# Power.net
KiCad netlist of a schematic drawn in Altium Designer
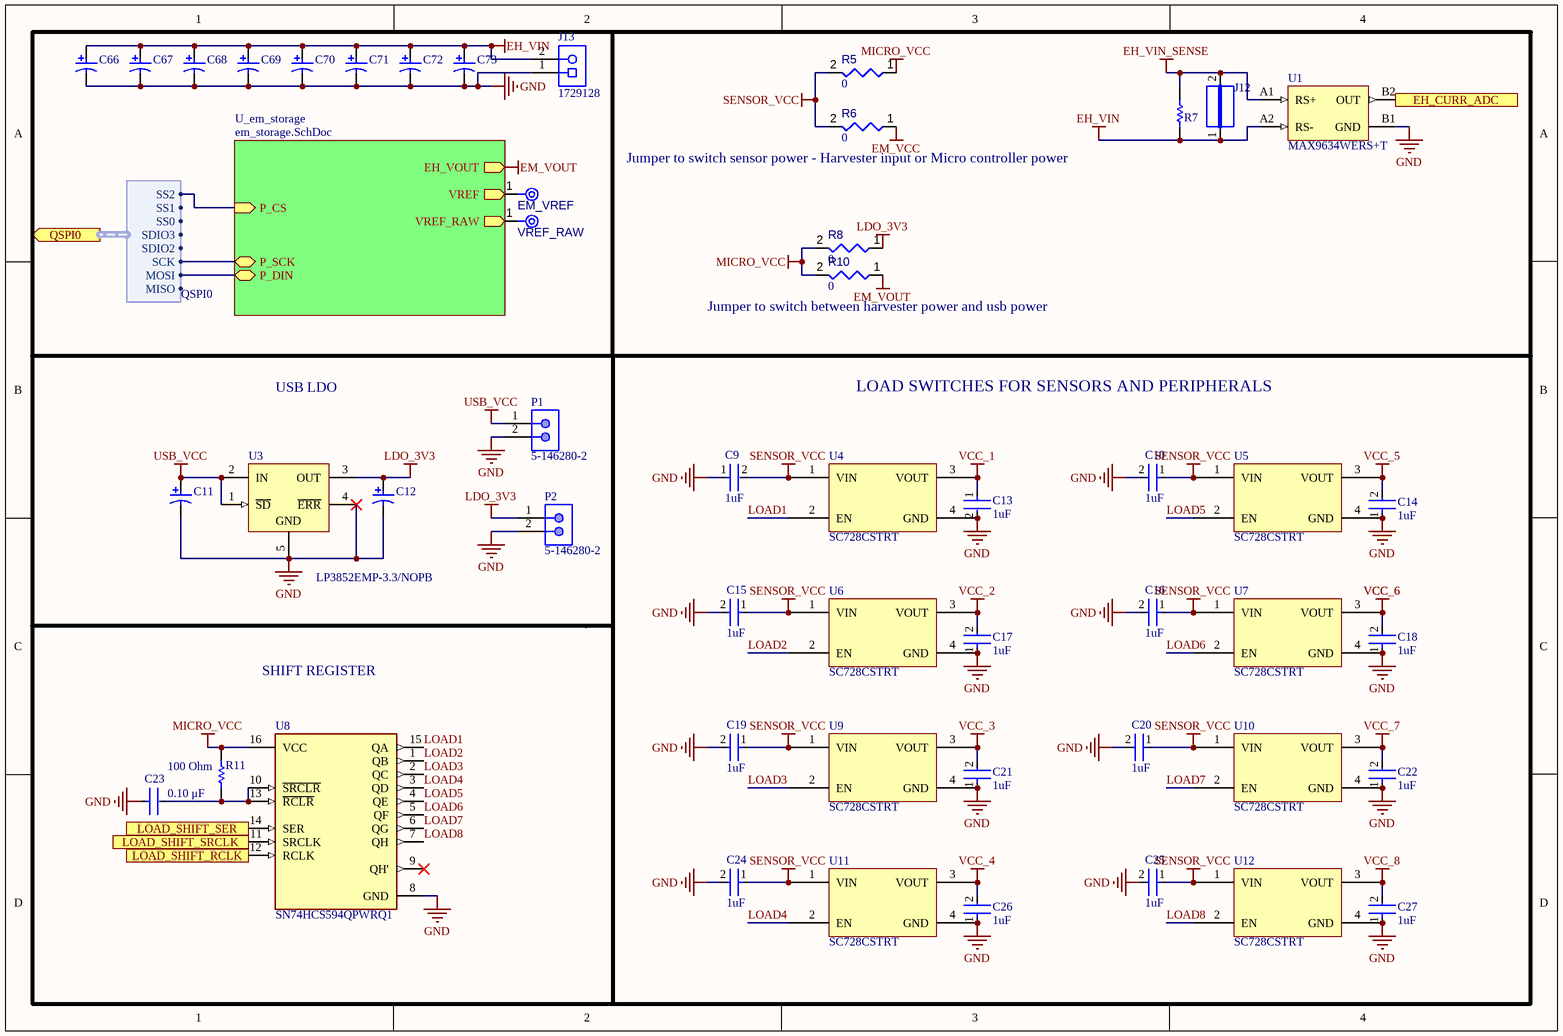
[diagram p0: Power.SchDoc]

(export (version "E")
  (design (tool "Eeschema 10.0.6"))
  (components
    (comp (ref "C9")
      (value "GRT155R61C105KE01J")
      (footprint "FP-GRM15-0_1-MFG")
      (description "CAP CER 1UF 10V X5R 0402")
      (fields
        (field (name "OCTOPART") "https://octopart.com/grm155r61a105ke15d-murata-197442")
        (field (name "MANUFACTURER PART NUMBER") "GRM155R61A105KE15D")
        (field (name "CAPACITANCE") "1uF")
      )
      (libsource (lib "Altium Content Vault") (part "02cd4be3c70576c341d710602a673aa"))
    )
    (comp (ref "C10")
      (value "GRT155R61C105KE01J")
      (footprint "FP-GRM15-0_1-MFG")
      (description "CAP CER 1UF 10V X5R 0402")
      (fields
        (field (name "OCTOPART") "https://octopart.com/grm155r61a105ke15d-murata-197442")
        (field (name "MANUFACTURER PART NUMBER") "GRM155R61A105KE15D")
        (field (name "CAPACITANCE") "1uF")
      )
      (libsource (lib "Altium Content Vault") (part "02cd4be3c70576c341d710602a673aa"))
    )
    (comp (ref "C11")
      (value "T491D106K025AT")
      (footprint "KEMT-T491-D_L")
      (description "Tantalum Capacitor, 10 uF, +/- 10%, 25 V, -55 to 125 degC, 2-Pin SMD, RoHS, Tape and Reel")
      (fields (field (name "MANUFACTURER") "Kemet") (field (name "VOLTAGE") "25VDC"))
      (libsource (lib "Altium Content Vault") (part "CAP-P-2"))
    )
    (comp (ref "C12")
      (value "T491D106K025AT")
      (footprint "KEMT-T491-D_L")
      (description "Tantalum Capacitor, 10 uF, +/- 10%, 25 V, -55 to 125 degC, 2-Pin SMD, RoHS, Tape and Reel")
      (fields (field (name "MANUFACTURER") "Kemet") (field (name "VOLTAGE") "25VDC"))
      (libsource (lib "Altium Content Vault") (part "CAP-P-2"))
    )
    (comp (ref "C13")
      (value "GRT155R61C105KE01J")
      (footprint "FP-GRM15-0_1-MFG")
      (description "CAP CER 1UF 10V X5R 0402")
      (fields
        (field (name "OCTOPART") "https://octopart.com/grm155r61a105ke15d-murata-197442")
        (field (name "MANUFACTURER PART NUMBER") "GRM155R61A105KE15D")
        (field (name "CAPACITANCE") "1uF")
      )
      (libsource (lib "Altium Content Vault") (part "02cd4be3c70576c341d710602a673aa"))
    )
    (comp (ref "C14")
      (value "GRT155R61C105KE01J")
      (footprint "FP-GRM15-0_1-MFG")
      (description "CAP CER 1UF 10V X5R 0402")
      (fields
        (field (name "OCTOPART") "https://octopart.com/grm155r61a105ke15d-murata-197442")
        (field (name "MANUFACTURER PART NUMBER") "GRM155R61A105KE15D")
        (field (name "CAPACITANCE") "1uF")
      )
      (libsource (lib "Altium Content Vault") (part "02cd4be3c70576c341d710602a673aa"))
    )
    (comp (ref "C15")
      (value "GRT155R61C105KE01J")
      (footprint "FP-GRM15-0_1-MFG")
      (description "CAP CER 1UF 10V X5R 0402")
      (fields
        (field (name "OCTOPART") "https://octopart.com/grm155r61a105ke15d-murata-197442")
        (field (name "MANUFACTURER PART NUMBER") "GRM155R61A105KE15D")
        (field (name "CAPACITANCE") "1uF")
      )
      (libsource (lib "Altium Content Vault") (part "02cd4be3c70576c341d710602a673aa"))
    )
    (comp (ref "C16")
      (value "GRT155R61C105KE01J")
      (footprint "FP-GRM15-0_1-MFG")
      (description "CAP CER 1UF 10V X5R 0402")
      (fields
        (field (name "OCTOPART") "https://octopart.com/grm155r61a105ke15d-murata-197442")
        (field (name "MANUFACTURER PART NUMBER") "GRM155R61A105KE15D")
        (field (name "CAPACITANCE") "1uF")
      )
      (libsource (lib "Altium Content Vault") (part "02cd4be3c70576c341d710602a673aa"))
    )
    (comp (ref "C17")
      (value "GRT155R61C105KE01J")
      (footprint "FP-GRM15-0_1-MFG")
      (description "CAP CER 1UF 10V X5R 0402")
      (fields
        (field (name "OCTOPART") "https://octopart.com/grm155r61a105ke15d-murata-197442")
        (field (name "MANUFACTURER PART NUMBER") "GRM155R61A105KE15D")
        (field (name "CAPACITANCE") "1uF")
      )
      (libsource (lib "Altium Content Vault") (part "02cd4be3c70576c341d710602a673aa"))
    )
    (comp (ref "C18")
      (value "GRT155R61C105KE01J")
      (footprint "FP-GRM15-0_1-MFG")
      (description "CAP CER 1UF 10V X5R 0402")
      (fields
        (field (name "OCTOPART") "https://octopart.com/grm155r61a105ke15d-murata-197442")
        (field (name "MANUFACTURER PART NUMBER") "GRM155R61A105KE15D")
        (field (name "CAPACITANCE") "1uF")
      )
      (libsource (lib "Altium Content Vault") (part "02cd4be3c70576c341d710602a673aa"))
    )
    (comp (ref "C19")
      (value "GRT155R61C105KE01J")
      (footprint "FP-GRM15-0_1-MFG")
      (description "CAP CER 1UF 10V X5R 0402")
      (fields
        (field (name "OCTOPART") "https://octopart.com/grm155r61a105ke15d-murata-197442")
        (field (name "MANUFACTURER PART NUMBER") "GRM155R61A105KE15D")
        (field (name "CAPACITANCE") "1uF")
      )
      (libsource (lib "Altium Content Vault") (part "02cd4be3c70576c341d710602a673aa"))
    )
    (comp (ref "C20")
      (value "GRT155R61C105KE01J")
      (footprint "FP-GRM15-0_1-MFG")
      (description "CAP CER 1UF 10V X5R 0402")
      (fields
        (field (name "OCTOPART") "https://octopart.com/grm155r61a105ke15d-murata-197442")
        (field (name "MANUFACTURER PART NUMBER") "GRM155R61A105KE15D")
        (field (name "CAPACITANCE") "1uF")
      )
      (libsource (lib "Altium Content Vault") (part "02cd4be3c70576c341d710602a673aa"))
    )
    (comp (ref "C21")
      (value "GRT155R61C105KE01J")
      (footprint "FP-GRM15-0_1-MFG")
      (description "CAP CER 1UF 10V X5R 0402")
      (fields
        (field (name "OCTOPART") "https://octopart.com/grm155r61a105ke15d-murata-197442")
        (field (name "MANUFACTURER PART NUMBER") "GRM155R61A105KE15D")
        (field (name "CAPACITANCE") "1uF")
      )
      (libsource (lib "Altium Content Vault") (part "02cd4be3c70576c341d710602a673aa"))
    )
    (comp (ref "C22")
      (value "GRT155R61C105KE01J")
      (footprint "FP-GRM15-0_1-MFG")
      (description "CAP CER 1UF 10V X5R 0402")
      (fields
        (field (name "OCTOPART") "https://octopart.com/grm155r61a105ke15d-murata-197442")
        (field (name "MANUFACTURER PART NUMBER") "GRM155R61A105KE15D")
        (field (name "CAPACITANCE") "1uF")
      )
      (libsource (lib "Altium Content Vault") (part "02cd4be3c70576c341d710602a673aa"))
    )
    (comp (ref "C23")
      (value "C0402C104K8PACTU")
      (footprint "FP-C0402-BB-MFG")
      (description "CAP CER 0.1UF 10V X5R 0402")
      (fields
        (field (name "CAPACITANCE") "0.10 μF")
        (field (name "MANUFACTURER") "Kemet")
        (field (name "TOLERANCE") "0.1")
      )
      (libsource (lib "Altium Content Vault") (part "b4654b650e69147ec39a6b967a45e02"))
    )
    (comp (ref "C24")
      (value "GRT155R61C105KE01J")
      (footprint "FP-GRM15-0_1-MFG")
      (description "CAP CER 1UF 10V X5R 0402")
      (fields
        (field (name "OCTOPART") "https://octopart.com/grm155r61a105ke15d-murata-197442")
        (field (name "MANUFACTURER PART NUMBER") "GRM155R61A105KE15D")
        (field (name "CAPACITANCE") "1uF")
      )
      (libsource (lib "Altium Content Vault") (part "02cd4be3c70576c341d710602a673aa"))
    )
    (comp (ref "C25")
      (value "GRT155R61C105KE01J")
      (footprint "FP-GRM15-0_1-MFG")
      (description "CAP CER 1UF 10V X5R 0402")
      (fields
        (field (name "OCTOPART") "https://octopart.com/grm155r61a105ke15d-murata-197442")
        (field (name "MANUFACTURER PART NUMBER") "GRM155R61A105KE15D")
        (field (name "CAPACITANCE") "1uF")
      )
      (libsource (lib "Altium Content Vault") (part "02cd4be3c70576c341d710602a673aa"))
    )
    (comp (ref "C26")
      (value "GRT155R61C105KE01J")
      (footprint "FP-GRM15-0_1-MFG")
      (description "CAP CER 1UF 10V X5R 0402")
      (fields
        (field (name "OCTOPART") "https://octopart.com/grm155r61a105ke15d-murata-197442")
        (field (name "MANUFACTURER PART NUMBER") "GRM155R61A105KE15D")
        (field (name "CAPACITANCE") "1uF")
      )
      (libsource (lib "Altium Content Vault") (part "02cd4be3c70576c341d710602a673aa"))
    )
    (comp (ref "C27")
      (value "GRT155R61C105KE01J")
      (footprint "FP-GRM15-0_1-MFG")
      (description "CAP CER 1UF 10V X5R 0402")
      (fields
        (field (name "OCTOPART") "https://octopart.com/grm155r61a105ke15d-murata-197442")
        (field (name "MANUFACTURER PART NUMBER") "GRM155R61A105KE15D")
        (field (name "CAPACITANCE") "1uF")
      )
      (libsource (lib "Altium Content Vault") (part "02cd4be3c70576c341d710602a673aa"))
    )
    (comp (ref "C66")
      (value "T491D106K025AT")
      (footprint "KEMT-T491-D_L")
      (description "Tantalum Capacitor, 10 uF, +/- 10%, 25 V, -55 to 125 degC, 2-Pin SMD, RoHS, Tape and Reel")
      (fields (field (name "MANUFACTURER") "Kemet") (field (name "VOLTAGE") "25VDC"))
      (libsource (lib "Altium Content Vault") (part "CAP-P-2"))
    )
    (comp (ref "C67")
      (value "T491D106K025AT")
      (footprint "KEMT-T491-D_L")
      (description "Tantalum Capacitor, 10 uF, +/- 10%, 25 V, -55 to 125 degC, 2-Pin SMD, RoHS, Tape and Reel")
      (fields (field (name "MANUFACTURER") "Kemet") (field (name "VOLTAGE") "25VDC"))
      (libsource (lib "Altium Content Vault") (part "CAP-P-2"))
    )
    (comp (ref "C68")
      (value "T491D106K025AT")
      (footprint "KEMT-T491-D_L")
      (description "Tantalum Capacitor, 10 uF, +/- 10%, 25 V, -55 to 125 degC, 2-Pin SMD, RoHS, Tape and Reel")
      (fields (field (name "MANUFACTURER") "Kemet") (field (name "VOLTAGE") "25VDC"))
      (libsource (lib "Altium Content Vault") (part "CAP-P-2"))
    )
    (comp (ref "C69")
      (value "T491D106K025AT")
      (footprint "KEMT-T491-D_L")
      (description "Tantalum Capacitor, 10 uF, +/- 10%, 25 V, -55 to 125 degC, 2-Pin SMD, RoHS, Tape and Reel")
      (fields (field (name "MANUFACTURER") "Kemet") (field (name "VOLTAGE") "25VDC"))
      (libsource (lib "Altium Content Vault") (part "CAP-P-2"))
    )
    (comp (ref "C70")
      (value "T491D106K025AT")
      (footprint "KEMT-T491-D_L")
      (description "Tantalum Capacitor, 10 uF, +/- 10%, 25 V, -55 to 125 degC, 2-Pin SMD, RoHS, Tape and Reel")
      (fields (field (name "MANUFACTURER") "Kemet") (field (name "VOLTAGE") "25VDC"))
      (libsource (lib "Altium Content Vault") (part "CAP-P-2"))
    )
    (comp (ref "C71")
      (value "T491D106K025AT")
      (footprint "KEMT-T491-D_L")
      (description "Tantalum Capacitor, 10 uF, +/- 10%, 25 V, -55 to 125 degC, 2-Pin SMD, RoHS, Tape and Reel")
      (fields (field (name "MANUFACTURER") "Kemet") (field (name "VOLTAGE") "25VDC"))
      (libsource (lib "Altium Content Vault") (part "CAP-P-2"))
    )
    (comp (ref "C72")
      (value "T491D106K025AT")
      (footprint "KEMT-T491-D_L")
      (description "Tantalum Capacitor, 10 uF, +/- 10%, 25 V, -55 to 125 degC, 2-Pin SMD, RoHS, Tape and Reel")
      (fields (field (name "MANUFACTURER") "Kemet") (field (name "VOLTAGE") "25VDC"))
      (libsource (lib "Altium Content Vault") (part "CAP-P-2"))
    )
    (comp (ref "C73")
      (value "T491D106K025AT")
      (footprint "KEMT-T491-D_L")
      (description "Tantalum Capacitor, 10 uF, +/- 10%, 25 V, -55 to 125 degC, 2-Pin SMD, RoHS, Tape and Reel")
      (fields (field (name "MANUFACTURER") "Kemet") (field (name "VOLTAGE") "25VDC"))
      (libsource (lib "Altium Content Vault") (part "CAP-P-2"))
    )
    (comp (ref "EM_VREF")
      (value "TPAD6R")
      (footprint "TP06R")
      (description "0.6mm round")
      (libsource (lib "Supersensor") (part "CMP-001-0001-4"))
    )
    (comp (ref "J12") (value "JUMPER") (footprint "JUMPER") (libsource (lib "Supersensor") (part "JUMPER")))
    (comp (ref "J13")
      (value "1729128")
      (footprint "PHOE-1729128-2_V")
      (description "PCB Terminal Block, 13.5 A, 400 V, 2-Pin THD, RoHS, Bulk")
      (fields (field (name "MANUFACTURER") "Phoenix Contact"))
      (libsource (lib "Altium Content Vault") (part "CN-2P-F-R2"))
    )
    (comp (ref "P1")
      (value "5-146280-2")
      (footprint "TECO-5-146280-2_V")
      (fields (field (name "MANUFACTURER") "TE Connectivity"))
      (libsource (lib "Altium Content Vault") (part "CN-1P-M-R2"))
    )
    (comp (ref "P2")
      (value "5-146280-2")
      (footprint "TECO-5-146280-2_V")
      (fields (field (name "MANUFACTURER") "TE Connectivity"))
      (libsource (lib "Altium Content Vault") (part "CN-1P-M-R2"))
    )
    (comp (ref "R5")
      (value "0")
      (footprint "RESC0402(1005)_L")
      (description "Jumper 0402")
      (libsource (lib "Supersensor") (part "RES-2"))
    )
    (comp (ref "R6")
      (value "0")
      (footprint "RESC0402(1005)_L")
      (description "Jumper 0402")
      (libsource (lib "Supersensor") (part "RES-2"))
    )
    (comp (ref "R7")
      (value "WSL0603R0300FEA18")
      (footprint "RESC1508X46X38ML25T25")
      (fields (field (name "MANUFACTURER") "Vishay Dale"))
      (libsource (lib "Altium Content Vault") (part "RES"))
    )
    (comp (ref "R8")
      (value "0")
      (footprint "RESC0402(1005)_L")
      (description "Jumper 0402")
      (libsource (lib "Supersensor") (part "RES-2"))
    )
    (comp (ref "R10")
      (value "0")
      (footprint "RESC0402(1005)_L")
      (description "Jumper 0402")
      (libsource (lib "Supersensor") (part "RES-2"))
    )
    (comp (ref "R11")
      (value "ERJ-2RKF1000X")
      (footprint "RESC1005X40X25LL05T05")
      (description "Chip Resistor, 100 Ohm, +/- 1%, 100 mW, -55 to 155 degC, 0402 (1005 Metric), RoHS, Tape and Reel")
      (fields
        (field (name "MANUFACTURER") "Basic Passives")
        (field (name "TOLERANCE") "1%")
        (field (name "RESISTANCE") "100 Ohm")
      )
      (libsource (lib "Altium Content Vault") (part "RES-2"))
    )
    (comp (ref "U1")
      (value "MAX9634WERS+T")
      (footprint "MAXM-R41A1+1")
      (libsource (lib "Altium Content Vault") (part "MAX9938_9634-X4"))
    )
    (comp (ref "U3")
      (value "LP3852EMP-3.3/NOPB")
      (footprint "NDC0005A_L")
      (description "1.5A Fast Ultra Low Dropout Linear Regulator, 5-pin SOT-223, Pb-Free")
      (fields (field (name "MANUFACTURER") "Texas Instruments"))
      (libsource (lib "Altium Content Vault") (part "PM-REG-LP3871-SOT5"))
    )
    (comp (ref "U4")
      (value "SC728CSTRT")
      (footprint "CSp 4")
      (libsource (lib "Integrated_Library1") (part "SC728CSTRT"))
    )
    (comp (ref "U5")
      (value "SC728CSTRT")
      (footprint "CSp 4")
      (libsource (lib "Integrated_Library1") (part "SC728CSTRT"))
    )
    (comp (ref "U6")
      (value "SC728CSTRT")
      (footprint "CSp 4")
      (libsource (lib "Integrated_Library1") (part "SC728CSTRT"))
    )
    (comp (ref "U7")
      (value "SC728CSTRT")
      (footprint "CSp 4")
      (libsource (lib "Integrated_Library1") (part "SC728CSTRT"))
    )
    (comp (ref "U8")
      (value "SN74HCS594QPWRQ1")
      (footprint "FP-PW0016A-IPC_A")
      (description "AUTOMOTIVE 8-BIT SHIFT REGISTERS")
      (libsource (lib "Altium Content Vault") (part "ee4c9120f52ff91501c7aa2bff67eb2"))
    )
    (comp (ref "U9")
      (value "SC728CSTRT")
      (footprint "CSp 4")
      (libsource (lib "Integrated_Library1") (part "SC728CSTRT"))
    )
    (comp (ref "U10")
      (value "SC728CSTRT")
      (footprint "CSp 4")
      (libsource (lib "Integrated_Library1") (part "SC728CSTRT"))
    )
    (comp (ref "U11")
      (value "SC728CSTRT")
      (footprint "CSp 4")
      (libsource (lib "Integrated_Library1") (part "SC728CSTRT"))
    )
    (comp (ref "U12")
      (value "SC728CSTRT")
      (footprint "CSp 4")
      (libsource (lib "Integrated_Library1") (part "SC728CSTRT"))
    )
    (comp (ref "VREF_RAW")
      (value "TPAD6R")
      (footprint "TP06R")
      (description "0.6mm round")
      (libsource (lib "Supersensor") (part "CMP-001-0001-4"))
    )
  )
  (nets
    (net (code "2") (name "/EH_CURR_ADC") (class "Default")
      (node (ref "U1") (pin "B2") (pinfunction "OUT_B2") (pintype "output"))
    )
    (net (code "3") (name "/LOAD1") (class "Default")
      (node (ref "U4") (pin "2") (pinfunction "EN_2") (pintype "passive"))
      (node (ref "U8") (pin "15") (pinfunction "QA_15") (pintype "output"))
    )
    (net (code "4") (name "/LOAD2") (class "Default")
      (node (ref "U6") (pin "2") (pinfunction "EN_2") (pintype "passive"))
      (node (ref "U8") (pin "1") (pinfunction "QB_1") (pintype "output"))
    )
    (net (code "5") (name "/LOAD3") (class "Default")
      (node (ref "U8") (pin "2") (pinfunction "QC_2") (pintype "output"))
      (node (ref "U9") (pin "2") (pinfunction "EN_2") (pintype "passive"))
    )
    (net (code "6") (name "/LOAD4") (class "Default")
      (node (ref "U11") (pin "2") (pinfunction "EN_2") (pintype "passive"))
      (node (ref "U8") (pin "3") (pinfunction "QD_3") (pintype "output"))
    )
    (net (code "7") (name "/LOAD5") (class "Default")
      (node (ref "U5") (pin "2") (pinfunction "EN_2") (pintype "passive"))
      (node (ref "U8") (pin "4") (pinfunction "QE_4") (pintype "output"))
    )
    (net (code "8") (name "/LOAD6") (class "Default")
      (node (ref "U7") (pin "2") (pinfunction "EN_2") (pintype "passive"))
      (node (ref "U8") (pin "5") (pinfunction "QF_5") (pintype "output"))
    )
    (net (code "9") (name "/LOAD7") (class "Default")
      (node (ref "U10") (pin "2") (pinfunction "EN_2") (pintype "passive"))
      (node (ref "U8") (pin "6") (pinfunction "QG_6") (pintype "output"))
    )
    (net (code "10") (name "/LOAD8") (class "Default")
      (node (ref "U12") (pin "2") (pinfunction "EN_2") (pintype "passive"))
      (node (ref "U8") (pin "7") (pinfunction "QH_7") (pintype "output"))
    )
    (net (code "11") (name "/LOAD_SHIFT_RCLK") (class "Default")
      (node (ref "U8") (pin "12") (pinfunction "RCLK_12") (pintype "input"))
    )
    (net (code "12") (name "/LOAD_SHIFT_SER") (class "Default")
      (node (ref "U8") (pin "14") (pinfunction "SER_14") (pintype "input"))
    )
    (net (code "13") (name "/LOAD_SHIFT_SRCLK") (class "Default")
      (node (ref "U8") (pin "11") (pinfunction "SRCLK_11") (pintype "input"))
    )
    (net (code "17") (name "/VREF") (class "Default")
      (node (ref "EM_VREF") (pin "1") (pinfunction "TP_1") (pintype "passive"))
    )
    (net (code "18") (name "/VREF_RAW") (class "Default")
      (node (ref "VREF_RAW") (pin "1") (pinfunction "TP_1") (pintype "passive"))
    )
    (net (code "20") (name "EH_VIN") (class "Default")
      (node (ref "C66") (pin "1") (pinfunction "1_1") (pintype "passive"))
      (node (ref "C67") (pin "1") (pinfunction "1_1") (pintype "passive"))
      (node (ref "C68") (pin "1") (pinfunction "1_1") (pintype "passive"))
      (node (ref "C69") (pin "1") (pinfunction "1_1") (pintype "passive"))
      (node (ref "C70") (pin "1") (pinfunction "1_1") (pintype "passive"))
      (node (ref "C71") (pin "1") (pinfunction "1_1") (pintype "passive"))
      (node (ref "C72") (pin "1") (pinfunction "1_1") (pintype "passive"))
      (node (ref "C73") (pin "1") (pinfunction "1_1") (pintype "passive"))
      (node (ref "J12") (pin "1") (pinfunction "1_1") (pintype "passive"))
      (node (ref "J13") (pin "2") (pinfunction "2_2") (pintype "passive"))
      (node (ref "R7") (pin "1") (pinfunction "1_1") (pintype "passive"))
      (node (ref "U1") (pin "A2") (pinfunction "RS-_A2") (pintype "input"))
    )
    (net (code "21") (name "EH_VIN_SENSE") (class "Default")
      (node (ref "J12") (pin "2") (pinfunction "2_2") (pintype "passive"))
      (node (ref "R7") (pin "2") (pinfunction "2_2") (pintype "passive"))
      (node (ref "U1") (pin "A1") (pinfunction "RS+_A1") (pintype "input"))
    )
    (net (code "22") (name "EM_VCC") (class "Default")
      (node (ref "R6") (pin "1") (pinfunction "1_1") (pintype "passive"))
    )
    (net (code "23") (name "EM_VOUT") (class "Default")
      (node (ref "R10") (pin "1") (pinfunction "1_1") (pintype "passive"))
    )
    (net (code "24") (name "GND") (class "Default")
      (node (ref "C10") (pin "2") (pinfunction "2_2") (pintype "passive"))
      (node (ref "C11") (pin "2") (pinfunction "2_2") (pintype "passive"))
      (node (ref "C12") (pin "2") (pinfunction "2_2") (pintype "passive"))
      (node (ref "C13") (pin "2") (pinfunction "2_2") (pintype "passive"))
      (node (ref "C14") (pin "1") (pinfunction "1_1") (pintype "passive"))
      (node (ref "C15") (pin "2") (pinfunction "2_2") (pintype "passive"))
      (node (ref "C16") (pin "2") (pinfunction "2_2") (pintype "passive"))
      (node (ref "C17") (pin "1") (pinfunction "1_1") (pintype "passive"))
      (node (ref "C18") (pin "1") (pinfunction "1_1") (pintype "passive"))
      (node (ref "C19") (pin "2") (pinfunction "2_2") (pintype "passive"))
      (node (ref "C20") (pin "2") (pinfunction "2_2") (pintype "passive"))
      (node (ref "C21") (pin "1") (pinfunction "1_1") (pintype "passive"))
      (node (ref "C22") (pin "1") (pinfunction "1_1") (pintype "passive"))
      (node (ref "C23") (pin "1") (pinfunction "1_1") (pintype "passive"))
      (node (ref "C24") (pin "2") (pinfunction "2_2") (pintype "passive"))
      (node (ref "C25") (pin "2") (pinfunction "2_2") (pintype "passive"))
      (node (ref "C26") (pin "1") (pinfunction "1_1") (pintype "passive"))
      (node (ref "C27") (pin "1") (pinfunction "1_1") (pintype "passive"))
      (node (ref "C66") (pin "2") (pinfunction "2_2") (pintype "passive"))
      (node (ref "C67") (pin "2") (pinfunction "2_2") (pintype "passive"))
      (node (ref "C68") (pin "2") (pinfunction "2_2") (pintype "passive"))
      (node (ref "C69") (pin "2") (pinfunction "2_2") (pintype "passive"))
      (node (ref "C70") (pin "2") (pinfunction "2_2") (pintype "passive"))
      (node (ref "C71") (pin "2") (pinfunction "2_2") (pintype "passive"))
      (node (ref "C72") (pin "2") (pinfunction "2_2") (pintype "passive"))
      (node (ref "C73") (pin "2") (pinfunction "2_2") (pintype "passive"))
      (node (ref "C9") (pin "1") (pinfunction "1_1") (pintype "passive"))
      (node (ref "J13") (pin "1") (pinfunction "1_1") (pintype "passive"))
      (node (ref "P1") (pin "2") (pinfunction "2_2") (pintype "passive"))
      (node (ref "P2") (pin "2") (pinfunction "2_2") (pintype "passive"))
      (node (ref "U1") (pin "B1") (pinfunction "GND_B1") (pintype "power_in"))
      (node (ref "U10") (pin "4") (pinfunction "GND_4") (pintype "passive"))
      (node (ref "U11") (pin "4") (pinfunction "GND_4") (pintype "passive"))
      (node (ref "U12") (pin "4") (pinfunction "GND_4") (pintype "passive"))
      (node (ref "U3") (pin "4") (pinfunction "~{ERR}_4") (pintype "open_collector"))
      (node (ref "U3") (pin "5") (pinfunction "GND_5") (pintype "power_in"))
      (node (ref "U4") (pin "4") (pinfunction "GND_4") (pintype "passive"))
      (node (ref "U5") (pin "4") (pinfunction "GND_4") (pintype "passive"))
      (node (ref "U6") (pin "4") (pinfunction "GND_4") (pintype "passive"))
      (node (ref "U7") (pin "4") (pinfunction "GND_4") (pintype "passive"))
      (node (ref "U8") (pin "8") (pinfunction "GND_8") (pintype "power_in"))
      (node (ref "U9") (pin "4") (pinfunction "GND_4") (pintype "passive"))
    )
    (net (code "25") (name "LDO_3V3") (class "Default")
      (node (ref "C12") (pin "1") (pinfunction "1_1") (pintype "passive"))
      (node (ref "P2") (pin "1") (pinfunction "1_1") (pintype "passive"))
      (node (ref "R8") (pin "1") (pinfunction "1_1") (pintype "passive"))
      (node (ref "U3") (pin "3") (pinfunction "OUT_3") (pintype "power_in"))
    )
    (net (code "26") (name "MICRO_VCC") (class "Default")
      (node (ref "R10") (pin "2") (pinfunction "2_2") (pintype "passive"))
      (node (ref "R11") (pin "2") (pinfunction "2_2") (pintype "passive"))
      (node (ref "R5") (pin "1") (pinfunction "1_1") (pintype "passive"))
      (node (ref "R8") (pin "2") (pinfunction "2_2") (pintype "passive"))
      (node (ref "U8") (pin "16") (pinfunction "VCC_16") (pintype "power_in"))
    )
    (net (code "27") (name "Net-(U8-~{RCLR})") (class "Default")
      (node (ref "C23") (pin "2") (pinfunction "2_2") (pintype "passive"))
      (node (ref "R11") (pin "1") (pinfunction "1_1") (pintype "passive"))
      (node (ref "U8") (pin "10") (pinfunction "~{SRCLR}_10") (pintype "input"))
      (node (ref "U8") (pin "13") (pinfunction "~{RCLR}_13") (pintype "input"))
    )
    (net (code "28") (name "SENSOR_VCC") (class "Default")
      (node (ref "C10") (pin "1") (pinfunction "1_1") (pintype "passive"))
      (node (ref "C15") (pin "1") (pinfunction "1_1") (pintype "passive"))
      (node (ref "C16") (pin "1") (pinfunction "1_1") (pintype "passive"))
      (node (ref "C19") (pin "1") (pinfunction "1_1") (pintype "passive"))
      (node (ref "C20") (pin "1") (pinfunction "1_1") (pintype "passive"))
      (node (ref "C24") (pin "1") (pinfunction "1_1") (pintype "passive"))
      (node (ref "C25") (pin "1") (pinfunction "1_1") (pintype "passive"))
      (node (ref "C9") (pin "2") (pinfunction "2_2") (pintype "passive"))
      (node (ref "R5") (pin "2") (pinfunction "2_2") (pintype "passive"))
      (node (ref "R6") (pin "2") (pinfunction "2_2") (pintype "passive"))
      (node (ref "U10") (pin "1") (pinfunction "VIN_1") (pintype "passive"))
      (node (ref "U11") (pin "1") (pinfunction "VIN_1") (pintype "passive"))
      (node (ref "U12") (pin "1") (pinfunction "VIN_1") (pintype "passive"))
      (node (ref "U4") (pin "1") (pinfunction "VIN_1") (pintype "passive"))
      (node (ref "U5") (pin "1") (pinfunction "VIN_1") (pintype "passive"))
      (node (ref "U6") (pin "1") (pinfunction "VIN_1") (pintype "passive"))
      (node (ref "U7") (pin "1") (pinfunction "VIN_1") (pintype "passive"))
      (node (ref "U9") (pin "1") (pinfunction "VIN_1") (pintype "passive"))
    )
    (net (code "29") (name "USB_VCC") (class "Default")
      (node (ref "C11") (pin "1") (pinfunction "1_1") (pintype "passive"))
      (node (ref "P1") (pin "1") (pinfunction "1_1") (pintype "passive"))
      (node (ref "U3") (pin "1") (pinfunction "~{SD}_1") (pintype "input"))
      (node (ref "U3") (pin "2") (pinfunction "IN_2") (pintype "power_in"))
    )
    (net (code "30") (name "VCC_1") (class "Default")
      (node (ref "C13") (pin "1") (pinfunction "1_1") (pintype "passive"))
      (node (ref "U4") (pin "3") (pinfunction "VOUT_3") (pintype "passive"))
    )
    (net (code "31") (name "VCC_2") (class "Default")
      (node (ref "C17") (pin "2") (pinfunction "2_2") (pintype "passive"))
      (node (ref "U6") (pin "3") (pinfunction "VOUT_3") (pintype "passive"))
    )
    (net (code "32") (name "VCC_3") (class "Default")
      (node (ref "C21") (pin "2") (pinfunction "2_2") (pintype "passive"))
      (node (ref "U9") (pin "3") (pinfunction "VOUT_3") (pintype "passive"))
    )
    (net (code "33") (name "VCC_4") (class "Default")
      (node (ref "C26") (pin "2") (pinfunction "2_2") (pintype "passive"))
      (node (ref "U11") (pin "3") (pinfunction "VOUT_3") (pintype "passive"))
    )
    (net (code "34") (name "VCC_5") (class "Default")
      (node (ref "C14") (pin "2") (pinfunction "2_2") (pintype "passive"))
      (node (ref "U5") (pin "3") (pinfunction "VOUT_3") (pintype "passive"))
    )
    (net (code "35") (name "VCC_6") (class "Default")
      (node (ref "C18") (pin "2") (pinfunction "2_2") (pintype "passive"))
      (node (ref "U7") (pin "3") (pinfunction "VOUT_3") (pintype "passive"))
    )
    (net (code "36") (name "VCC_7") (class "Default")
      (node (ref "C22") (pin "2") (pinfunction "2_2") (pintype "passive"))
      (node (ref "U10") (pin "3") (pinfunction "VOUT_3") (pintype "passive"))
    )
    (net (code "37") (name "VCC_8") (class "Default")
      (node (ref "C27") (pin "2") (pinfunction "2_2") (pintype "passive"))
      (node (ref "U12") (pin "3") (pinfunction "VOUT_3") (pintype "passive"))
    )
    (net (code "38") (name "unconnected-(U8-QH'-Pad9)") (class "Default")
      (node (ref "U8") (pin "9") (pinfunction "QH'_9") (pintype "output+no_connect"))
    )
  )
)
